# Sheet5_LCD.net
KiCad netlist of a schematic drawn in Altium Designer
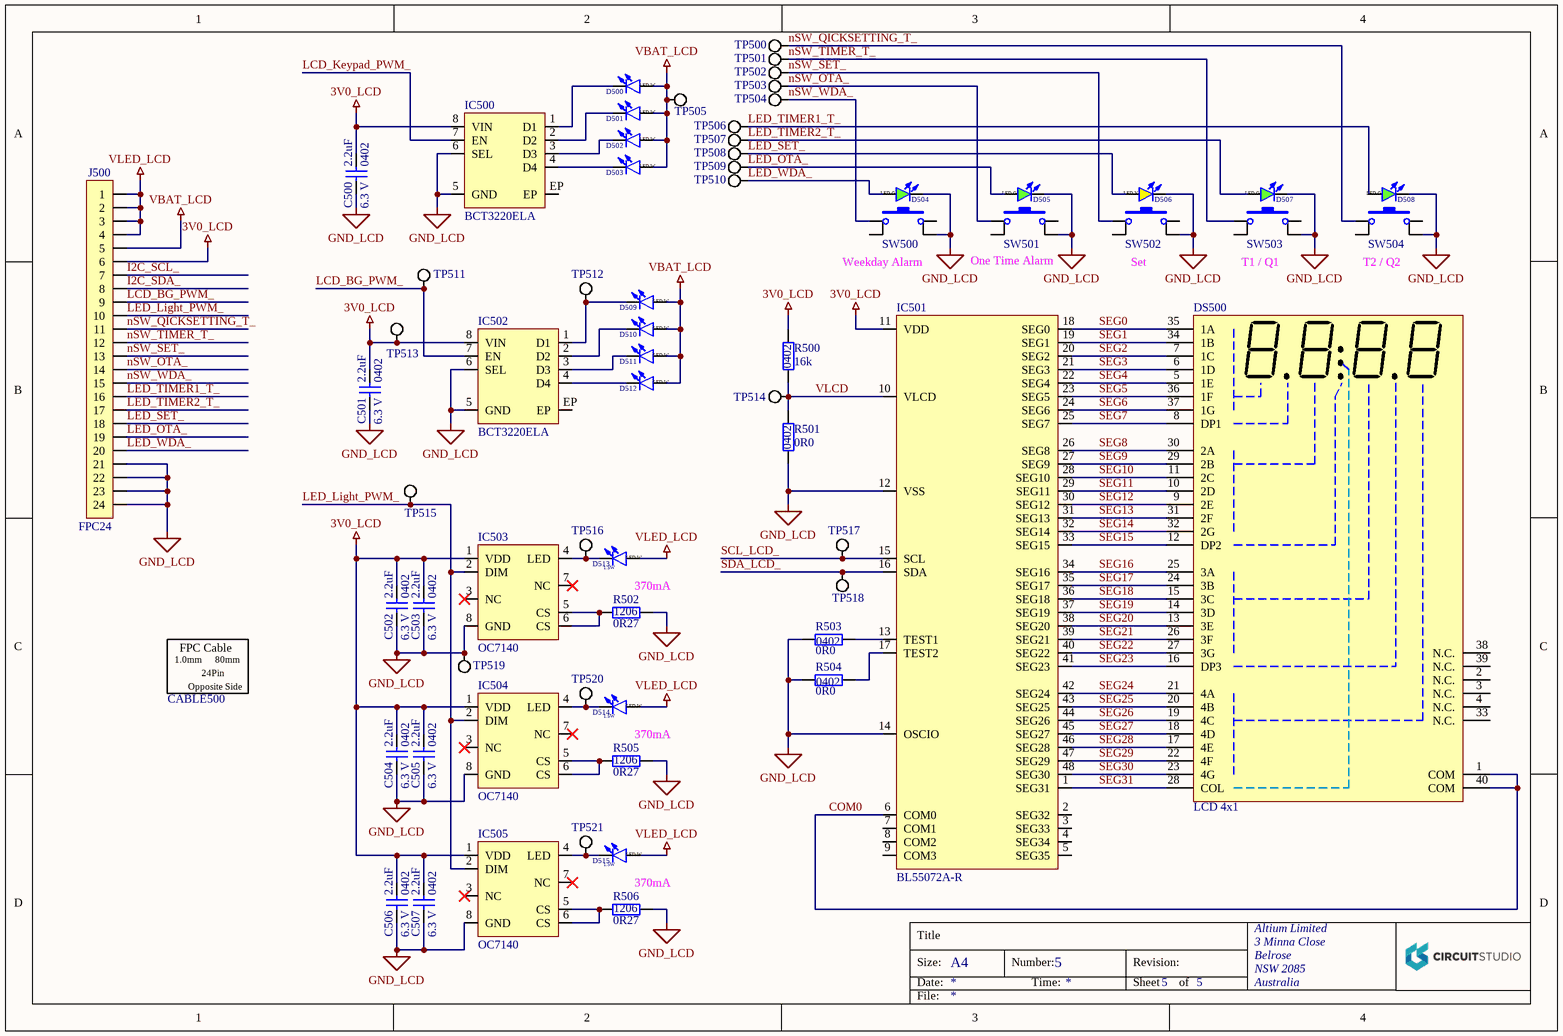
[diagram p0: Sheet5_LCD.SchDoc]

(export (version "E")
  (design (tool "Eeschema 10.0.6"))
  (components
    (comp (ref "C500")
      (value "C 2.2uF 0402 6.3V")
      (footprint "0402")
      (description "CAP CER 2.2UF 6.3V X6T 0402")
      (fields
        (field (name "MANUFACTURER") "Murata Electronics")
        (field (name "MANUFACTURER PART NUMBER") "GRM155D80J225ME95D")
        (field (name "CAPACITANCE") "2.2uF")
        (field (name "VOLTAGE") "6.3 V")
      )
      (libsource (lib "CS_Part_Library") (part "CAP_2.2uF_6V3_0402"))
    )
    (comp (ref "C501")
      (value "C 2.2uF 0402 6.3V")
      (footprint "0402")
      (description "CAP CER 2.2UF 6.3V X6T 0402")
      (fields
        (field (name "MANUFACTURER") "Murata Electronics")
        (field (name "MANUFACTURER PART NUMBER") "GRM155D80J225ME95D")
        (field (name "CAPACITANCE") "2.2uF")
        (field (name "VOLTAGE") "6.3 V")
      )
      (libsource (lib "CS_Part_Library") (part "CAP_2.2uF_6V3_0402"))
    )
    (comp (ref "C502")
      (value "C 2.2uF 0402 6.3V")
      (footprint "0402")
      (description "CAP CER 2.2UF 6.3V X6T 0402")
      (fields
        (field (name "MANUFACTURER") "Murata Electronics")
        (field (name "MANUFACTURER PART NUMBER") "GRM155D80J225ME95D")
        (field (name "CAPACITANCE") "2.2uF")
        (field (name "VOLTAGE") "6.3 V")
      )
      (libsource (lib "CS_Part_Library") (part "CAP_2.2uF_6V3_0402"))
    )
    (comp (ref "C503")
      (value "C 2.2uF 0402 6.3V")
      (footprint "0402")
      (description "CAP CER 2.2UF 6.3V X6T 0402")
      (fields
        (field (name "MANUFACTURER") "Murata Electronics")
        (field (name "MANUFACTURER PART NUMBER") "GRM155D80J225ME95D")
        (field (name "CAPACITANCE") "2.2uF")
        (field (name "VOLTAGE") "6.3 V")
      )
      (libsource (lib "CS_Part_Library") (part "CAP_2.2uF_6V3_0402"))
    )
    (comp (ref "C504")
      (value "C 2.2uF 0402 6.3V")
      (footprint "0402")
      (description "CAP CER 2.2UF 6.3V X6T 0402")
      (fields
        (field (name "MANUFACTURER") "Murata Electronics")
        (field (name "MANUFACTURER PART NUMBER") "GRM155D80J225ME95D")
        (field (name "CAPACITANCE") "2.2uF")
        (field (name "VOLTAGE") "6.3 V")
      )
      (libsource (lib "CS_Part_Library") (part "CAP_2.2uF_6V3_0402"))
    )
    (comp (ref "C505")
      (value "C 2.2uF 0402 6.3V")
      (footprint "0402")
      (description "CAP CER 2.2UF 6.3V X6T 0402")
      (fields
        (field (name "MANUFACTURER") "Murata Electronics")
        (field (name "MANUFACTURER PART NUMBER") "GRM155D80J225ME95D")
        (field (name "CAPACITANCE") "2.2uF")
        (field (name "VOLTAGE") "6.3 V")
      )
      (libsource (lib "CS_Part_Library") (part "CAP_2.2uF_6V3_0402"))
    )
    (comp (ref "C506")
      (value "C 2.2uF 0402 6.3V")
      (footprint "0402")
      (description "CAP CER 2.2UF 6.3V X6T 0402")
      (fields
        (field (name "MANUFACTURER") "Murata Electronics")
        (field (name "MANUFACTURER PART NUMBER") "GRM155D80J225ME95D")
        (field (name "CAPACITANCE") "2.2uF")
        (field (name "VOLTAGE") "6.3 V")
      )
      (libsource (lib "CS_Part_Library") (part "CAP_2.2uF_6V3_0402"))
    )
    (comp (ref "C507")
      (value "C 2.2uF 0402 6.3V")
      (footprint "0402")
      (description "CAP CER 2.2UF 6.3V X6T 0402")
      (fields
        (field (name "MANUFACTURER") "Murata Electronics")
        (field (name "MANUFACTURER PART NUMBER") "GRM155D80J225ME95D")
        (field (name "CAPACITANCE") "2.2uF")
        (field (name "VOLTAGE") "6.3 V")
      )
      (libsource (lib "CS_Part_Library") (part "CAP_2.2uF_6V3_0402"))
    )
    (comp (ref "CABLE500")
      (value "FPC24p80mm")
      (description "FPC Cable 1mm Pitch 24Pin 80mm Opposite Sides")
      (fields
        (field (name "MANUFACTURER") "LX")
        (field (name "MANUFACTURER PART NUMBER") "C50299")
        (field (name "PITCH") "1.0mm")
        (field (name "LENGTH") "80mm")
        (field (name "MODE") "Opposite Side")
        (field (name "NOOFPINS") "24Pin")
      )
      (libsource (lib "Symbols") (part "CABLE_FPC24_80"))
    )
    (comp (ref "D500")
      (value "LED W")
      (footprint "LED_99-218UMC_side")
      (description "LED WHITE SIDE SMD")
      (fields
        (field (name "MANUFACTURER") "Everlight Elec")
        (field (name "MANUFACTURER PART NUMBER") "99-218UMC/1637CD/TR8-T")
      )
      (libsource (lib "CS_Part_Library") (part "D_LED_White_s"))
    )
    (comp (ref "D501")
      (value "LED W")
      (footprint "LED_99-218UMC_side")
      (description "LED WHITE SIDE SMD")
      (fields
        (field (name "MANUFACTURER") "Everlight Elec")
        (field (name "MANUFACTURER PART NUMBER") "99-218UMC/1637CD/TR8-T")
      )
      (libsource (lib "CS_Part_Library") (part "D_LED_White_s"))
    )
    (comp (ref "D502")
      (value "LED W")
      (footprint "LED_99-218UMC_side")
      (description "LED WHITE SIDE SMD")
      (fields
        (field (name "MANUFACTURER") "Everlight Elec")
        (field (name "MANUFACTURER PART NUMBER") "99-218UMC/1637CD/TR8-T")
      )
      (libsource (lib "CS_Part_Library") (part "D_LED_White_s"))
    )
    (comp (ref "D503")
      (value "LED W")
      (footprint "LED_99-218UMC_side")
      (description "LED WHITE SIDE SMD")
      (fields
        (field (name "MANUFACTURER") "Everlight Elec")
        (field (name "MANUFACTURER PART NUMBER") "99-218UMC/1637CD/TR8-T")
      )
      (libsource (lib "CS_Part_Library") (part "D_LED_White_s"))
    )
    (comp (ref "D504")
      (value "LED G")
      (footprint "LED_0603")
      (description "LED GREEN DIFFUSED 0603 SMD")
      (fields
        (field (name "MANUFACTURER") "OSRAM Opto Semiconductors Inc.")
        (field (name "MANUFACTURER PART NUMBER") "LT Q39G-Q1OO-25-1")
      )
      (libsource (lib "CS_Part_Library") (part "D_LED_Green_0603"))
    )
    (comp (ref "D505")
      (value "LED G")
      (footprint "LED_0603")
      (description "LED GREEN DIFFUSED 0603 SMD")
      (fields
        (field (name "MANUFACTURER") "OSRAM Opto Semiconductors Inc.")
        (field (name "MANUFACTURER PART NUMBER") "LT Q39G-Q1OO-25-1")
      )
      (libsource (lib "CS_Part_Library") (part "D_LED_Green_0603"))
    )
    (comp (ref "D506")
      (value "LED Y")
      (footprint "LED_0603")
      (description "LED YELLOW DIFFUSED")
      (fields
        (field (name "MANUFACTURER") "Stanley Electric Co")
        (field (name "MANUFACTURER PART NUMBER") "FKY1111C-TR")
      )
      (libsource (lib "CS_Part_Library") (part "D_LED_Yellow_0603"))
    )
    (comp (ref "D507")
      (value "LED G")
      (footprint "LED_0603")
      (description "LED GREEN DIFFUSED 0603 SMD")
      (fields
        (field (name "MANUFACTURER") "OSRAM Opto Semiconductors Inc.")
        (field (name "MANUFACTURER PART NUMBER") "LT Q39G-Q1OO-25-1")
      )
      (libsource (lib "CS_Part_Library") (part "D_LED_Green_0603"))
    )
    (comp (ref "D508")
      (value "LED G")
      (footprint "LED_0603")
      (description "LED GREEN DIFFUSED 0603 SMD")
      (fields
        (field (name "MANUFACTURER") "OSRAM Opto Semiconductors Inc.")
        (field (name "MANUFACTURER PART NUMBER") "LT Q39G-Q1OO-25-1")
      )
      (libsource (lib "CS_Part_Library") (part "D_LED_Green_0603"))
    )
    (comp (ref "D509")
      (value "LED W")
      (footprint "LED_99-218UMC_side")
      (description "LED WHITE SIDE SMD")
      (fields
        (field (name "MANUFACTURER") "Everlight Elec")
        (field (name "MANUFACTURER PART NUMBER") "99-218UMC/1637CD/TR8-T")
      )
      (libsource (lib "CS_Part_Library") (part "D_LED_White_s"))
    )
    (comp (ref "D510")
      (value "LED W")
      (footprint "LED_99-218UMC_side")
      (description "LED WHITE SIDE SMD")
      (fields
        (field (name "MANUFACTURER") "Everlight Elec")
        (field (name "MANUFACTURER PART NUMBER") "99-218UMC/1637CD/TR8-T")
      )
      (libsource (lib "CS_Part_Library") (part "D_LED_White_s"))
    )
    (comp (ref "D511")
      (value "LED W")
      (footprint "LED_99-218UMC_side")
      (description "LED WHITE SIDE SMD")
      (fields
        (field (name "MANUFACTURER") "Everlight Elec")
        (field (name "MANUFACTURER PART NUMBER") "99-218UMC/1637CD/TR8-T")
      )
      (libsource (lib "CS_Part_Library") (part "D_LED_White_s"))
    )
    (comp (ref "D512")
      (value "LED W")
      (footprint "LED_99-218UMC_side")
      (description "LED WHITE SIDE SMD")
      (fields
        (field (name "MANUFACTURER") "Everlight Elec")
        (field (name "MANUFACTURER PART NUMBER") "99-218UMC/1637CD/TR8-T")
      )
      (libsource (lib "CS_Part_Library") (part "D_LED_White_s"))
    )
    (comp (ref "D513")
      (value "LED W")
      (footprint "LED_3.5x3.15")
      (description "LED XLAMP WARM WHITE 3250K 4SMD")
      (fields
        (field (name "MANUFACTURER") "CreeLED, Inc.")
        (field (name "MANUFACTURER PART NUMBER") "MLEAWT-A1-0000-0003F7")
        (field (name "POWER") "1.5W")
      )
      (libsource (lib "CS_Part_Library") (part "D_LED_W_HP"))
    )
    (comp (ref "D514")
      (value "LED W")
      (footprint "LED_3.5x3.15")
      (description "LED XLAMP WARM WHITE 3250K 4SMD")
      (fields
        (field (name "MANUFACTURER") "CreeLED, Inc.")
        (field (name "MANUFACTURER PART NUMBER") "MLEAWT-A1-0000-0003F7")
        (field (name "POWER") "1.5W")
      )
      (libsource (lib "CS_Part_Library") (part "D_LED_W_HP"))
    )
    (comp (ref "D515")
      (value "LED W")
      (footprint "LED_3.5x3.15")
      (description "LED XLAMP WARM WHITE 3250K 4SMD")
      (fields
        (field (name "MANUFACTURER") "CreeLED, Inc.")
        (field (name "MANUFACTURER PART NUMBER") "MLEAWT-A1-0000-0003F7")
        (field (name "POWER") "1.5W")
      )
      (libsource (lib "CS_Part_Library") (part "D_LED_W_HP"))
    )
    (comp (ref "DS500")
      (value "LCD 4x1")
      (footprint "DISPL_7SEG_4")
      (description "LCD MOD 4 DIG 4 X 1 REFLECTIVE")
      (fields
        (field (name "MANUFACTURER") "Varitronix")
        (field (name "MANUFACTURER PART NUMBER") "VI-402-DP-RC-S")
      )
      (libsource (lib "Symbols") (part "DISPL_7SEG_4x1"))
    )
    (comp (ref "IC500")
      (value "BCT3220ELA")
      (footprint "VDFN-8-EP_2x2")
      (description "IC LED DRIVER 4 CH")
      (fields
        (field (name "MANUFACTURER") "BROADCHIP")
        (field (name "MANUFACTURER PART NUMBER") "BCT3220ELA-TR")
      )
      (libsource (lib "Symbols") (part "IC_LED_cntr_BCT3220ELA"))
    )
    (comp (ref "IC501")
      (value "BL55072A-R")
      (footprint "TSSOP-48")
      (description "IC LCD DRIVER 36SEG TSSOP-48")
      (fields (field (name "MANUFACTURER") "BL(Shanghai Belling)"))
      (libsource (lib "Symbols") (part "IC_LCD_cntr_BL55072A-R"))
    )
    (comp (ref "IC502")
      (value "BCT3220ELA")
      (footprint "VDFN-8-EP_2x2")
      (description "IC LED DRIVER 4 CH")
      (fields
        (field (name "MANUFACTURER") "BROADCHIP")
        (field (name "MANUFACTURER PART NUMBER") "BCT3220ELA-TR")
      )
      (libsource (lib "Symbols") (part "IC_LED_cntr_BCT3220ELA"))
    )
    (comp (ref "IC503")
      (value "OC7140")
      (footprint "SOIC-8-EP")
      (description "IC LED DRIVER 1 CH 2A ESOP8")
      (fields (field (name "MANUFACTURER") "OCX"))
      (libsource (lib "CS_Part_Library") (part "IC_LED_cntr_OC7140"))
    )
    (comp (ref "IC504")
      (value "OC7140")
      (footprint "SOIC-8-EP")
      (description "IC LED DRIVER 1 CH 2A ESOP8")
      (fields (field (name "MANUFACTURER") "OCX"))
      (libsource (lib "CS_Part_Library") (part "IC_LED_cntr_OC7140"))
    )
    (comp (ref "IC505")
      (value "OC7140")
      (footprint "SOIC-8-EP")
      (description "IC LED DRIVER 1 CH 2A ESOP8")
      (fields (field (name "MANUFACTURER") "OCX"))
      (libsource (lib "CS_Part_Library") (part "IC_LED_cntr_OC7140"))
    )
    (comp (ref "J500")
      (value "FPC24")
      (footprint "J_FPC_522712479")
      (description "CONN FPC BOT 24 PIN 1mm Pitch")
      (fields (field (name "MANUFACTURER") "MOLEX") (field (name "MANUFACTURER PART NUMBER") "522712479"))
      (libsource (lib "Symbols") (part "J_FPC24_DS"))
    )
    (comp (ref "R500")
      (value "R 16k 0402")
      (footprint "0402")
      (description "RES 16K OHM 1% 1/16W 0402")
      (fields
        (field (name "MANUFACTURER") "Stackpole Electronics Inc")
        (field (name "MANUFACTURER PART NUMBER") "RMCF0402FT16K0")
        (field (name "RESISTANCE") "16k")
      )
      (libsource (lib "CS_Part_Library") (part "R_16k_0402"))
    )
    (comp (ref "R501")
      (value "R 0R0 0402")
      (footprint "0402")
      (description "RES 0 OHM JUMPER 1/16W 0402")
      (fields
        (field (name "MANUFACTURER") "Stackpole Electronics Inc")
        (field (name "MANUFACTURER PART NUMBER") "RMCF0402ZT0R00")
        (field (name "RESISTANCE") "0R0")
      )
      (libsource (lib "CS_Part_Library") (part "R_0R0_0402"))
    )
    (comp (ref "R502")
      (value "R 0R27 1206")
      (footprint "1206")
      (description "RES 0.27 OHM 1% 1/3W 1206")
      (fields
        (field (name "MANUFACTURER") "RALEC")
        (field (name "MANUFACTURER PART NUMBER") "RTT06R270FTP")
        (field (name "RESISTANCE") "0R27")
      )
      (libsource (lib "CS_Part_Library") (part "R_0R27_1206"))
    )
    (comp (ref "R503")
      (value "R 0R0 0402")
      (footprint "0402")
      (description "RES 0 OHM JUMPER 1/16W 0402")
      (fields
        (field (name "MANUFACTURER") "Stackpole Electronics Inc")
        (field (name "MANUFACTURER PART NUMBER") "RMCF0402ZT0R00")
        (field (name "RESISTANCE") "0R0")
      )
      (libsource (lib "") (part "R_0R0_0402_1"))
    )
    (comp (ref "R504")
      (value "R 0R0 0402")
      (footprint "0402")
      (description "RES 0 OHM JUMPER 1/16W 0402")
      (fields
        (field (name "MANUFACTURER") "Stackpole Electronics Inc")
        (field (name "MANUFACTURER PART NUMBER") "RMCF0402ZT0R00")
        (field (name "RESISTANCE") "0R0")
      )
      (libsource (lib "") (part "R_0R0_0402_1"))
    )
    (comp (ref "R505")
      (value "R 0R27 1206")
      (footprint "1206")
      (description "RES 0.27 OHM 1% 1/3W 1206")
      (fields
        (field (name "MANUFACTURER") "RALEC")
        (field (name "MANUFACTURER PART NUMBER") "RTT06R270FTP")
        (field (name "RESISTANCE") "0R27")
      )
      (libsource (lib "CS_Part_Library") (part "R_0R27_1206"))
    )
    (comp (ref "R506")
      (value "R 0R27 1206")
      (footprint "1206")
      (description "RES 0.27 OHM 1% 1/3W 1206")
      (fields
        (field (name "MANUFACTURER") "RALEC")
        (field (name "MANUFACTURER PART NUMBER") "RTT06R270FTP")
        (field (name "RESISTANCE") "0R27")
      )
      (libsource (lib "CS_Part_Library") (part "R_0R27_1206"))
    )
    (comp (ref "SW500")
      (value "SW")
      (footprint "SW_BRIGHT_6.1x6.1")
      (description "SWITCH TACTILE SW-SMD")
      (fields
        (field (name "MANUFACTURER") "BRIGHT")
        (field (name "MANUFACTURER PART NUMBER") "TSA063G50-250")
      )
      (libsource (lib "CS_Part_Library") (part "SW_TactileSW_V_2"))
    )
    (comp (ref "SW501")
      (value "SW")
      (footprint "SW_BRIGHT_6.1x6.1")
      (description "SWITCH TACTILE SW-SMD")
      (fields
        (field (name "MANUFACTURER") "BRIGHT")
        (field (name "MANUFACTURER PART NUMBER") "TSA063G50-250")
      )
      (libsource (lib "CS_Part_Library") (part "SW_TactileSW_V_2"))
    )
    (comp (ref "SW502")
      (value "SW")
      (footprint "SW_BRIGHT_6.1x6.1")
      (description "SWITCH TACTILE SW-SMD")
      (fields
        (field (name "MANUFACTURER") "BRIGHT")
        (field (name "MANUFACTURER PART NUMBER") "TSA063G50-250")
      )
      (libsource (lib "CS_Part_Library") (part "SW_TactileSW_V_2"))
    )
    (comp (ref "SW503")
      (value "SW")
      (footprint "SW_BRIGHT_6.1x6.1")
      (description "SWITCH TACTILE SW-SMD")
      (fields
        (field (name "MANUFACTURER") "BRIGHT")
        (field (name "MANUFACTURER PART NUMBER") "TSA063G50-250")
      )
      (libsource (lib "CS_Part_Library") (part "SW_TactileSW_V_2"))
    )
    (comp (ref "SW504")
      (value "SW")
      (footprint "SW_BRIGHT_6.1x6.1")
      (description "SWITCH TACTILE SW-SMD")
      (fields
        (field (name "MANUFACTURER") "BRIGHT")
        (field (name "MANUFACTURER PART NUMBER") "TSA063G50-250")
      )
      (libsource (lib "CS_Part_Library") (part "SW_TactileSW_V_2"))
    )
    (comp (ref "TP500")
      (value "TP")
      (footprint "TP_1mm")
      (description "Test Point 1mm")
      (libsource (lib "CS_Part_Library") (part "TP_1mm"))
    )
    (comp (ref "TP501")
      (value "TP")
      (footprint "TP_1mm")
      (description "Test Point 1mm")
      (libsource (lib "CS_Part_Library") (part "TP_1mm"))
    )
    (comp (ref "TP502")
      (value "TP")
      (footprint "TP_1mm")
      (description "Test Point 1mm")
      (libsource (lib "CS_Part_Library") (part "TP_1mm"))
    )
    (comp (ref "TP503")
      (value "TP")
      (footprint "TP_1mm")
      (description "Test Point 1mm")
      (libsource (lib "CS_Part_Library") (part "TP_1mm"))
    )
    (comp (ref "TP504")
      (value "TP")
      (footprint "TP_1mm")
      (description "Test Point 1mm")
      (libsource (lib "CS_Part_Library") (part "TP_1mm"))
    )
    (comp (ref "TP505")
      (value "TP")
      (footprint "TP_1mm")
      (description "Test Point 1mm")
      (libsource (lib "CS_Part_Library") (part "TP_1mm"))
    )
    (comp (ref "TP506")
      (value "TP")
      (footprint "TP_1mm")
      (description "Test Point 1mm")
      (libsource (lib "CS_Part_Library") (part "TP_1mm"))
    )
    (comp (ref "TP507")
      (value "TP")
      (footprint "TP_1mm")
      (description "Test Point 1mm")
      (libsource (lib "CS_Part_Library") (part "TP_1mm"))
    )
    (comp (ref "TP508")
      (value "TP")
      (footprint "TP_1mm")
      (description "Test Point 1mm")
      (libsource (lib "CS_Part_Library") (part "TP_1mm"))
    )
    (comp (ref "TP509")
      (value "TP")
      (footprint "TP_1mm")
      (description "Test Point 1mm")
      (libsource (lib "CS_Part_Library") (part "TP_1mm"))
    )
    (comp (ref "TP510")
      (value "TP")
      (footprint "TP_1mm")
      (description "Test Point 1mm")
      (libsource (lib "CS_Part_Library") (part "TP_1mm"))
    )
    (comp (ref "TP511")
      (value "TP")
      (footprint "TP_1mm")
      (description "Test Point 1mm")
      (libsource (lib "CS_Part_Library") (part "TP_1mm"))
    )
    (comp (ref "TP512")
      (value "TP")
      (footprint "TP_1mm")
      (description "Test Point 1mm")
      (libsource (lib "CS_Part_Library") (part "TP_1mm"))
    )
    (comp (ref "TP513")
      (value "TP")
      (footprint "TP_1mm")
      (description "Test Point 1mm")
      (libsource (lib "CS_Part_Library") (part "TP_1mm"))
    )
    (comp (ref "TP514")
      (value "TP")
      (footprint "TP_1mm")
      (description "Test Point 1mm")
      (libsource (lib "CS_Part_Library") (part "TP_1mm"))
    )
    (comp (ref "TP515")
      (value "TP")
      (footprint "TP_1mm")
      (description "Test Point 1mm")
      (libsource (lib "CS_Part_Library") (part "TP_1mm"))
    )
    (comp (ref "TP516")
      (value "TP")
      (footprint "TP_1mm")
      (description "Test Point 1mm")
      (libsource (lib "CS_Part_Library") (part "TP_1mm"))
    )
    (comp (ref "TP517")
      (value "TP")
      (footprint "TP_1mm")
      (description "Test Point 1mm")
      (libsource (lib "CS_Part_Library") (part "TP_1mm"))
    )
    (comp (ref "TP518")
      (value "TP")
      (footprint "TP_1mm")
      (description "Test Point 1mm")
      (libsource (lib "CS_Part_Library") (part "TP_1mm"))
    )
    (comp (ref "TP519")
      (value "TP")
      (footprint "TP_1mm")
      (description "Test Point 1mm")
      (libsource (lib "CS_Part_Library") (part "TP_1mm"))
    )
    (comp (ref "TP520")
      (value "TP")
      (footprint "TP_1mm")
      (description "Test Point 1mm")
      (libsource (lib "CS_Part_Library") (part "TP_1mm"))
    )
    (comp (ref "TP521")
      (value "TP")
      (footprint "TP_1mm")
      (description "Test Point 1mm")
      (libsource (lib "CS_Part_Library") (part "TP_1mm"))
    )
  )
  (nets
    (net (code "1") (name "/COM0") (class "Default")
      (node (ref "DS500") (pin "1") (pinfunction "COM_1") (pintype "passive"))
      (node (ref "DS500") (pin "40") (pinfunction "COM_40") (pintype "passive"))
      (node (ref "IC501") (pin "6") (pinfunction "COM0_6") (pintype "passive"))
    )
    (net (code "2") (name "/I2C_SCL_") (class "Default")
      (node (ref "J500") (pin "7") (pinfunction "7_7") (pintype "passive"))
    )
    (net (code "3") (name "/I2C_SDA_") (class "Default")
      (node (ref "J500") (pin "8") (pinfunction "8_8") (pintype "passive"))
    )
    (net (code "4") (name "/LCD_BG_PWM_") (class "Default")
      (node (ref "IC502") (pin "7") (pinfunction "EN_7") (pintype "passive"))
      (node (ref "J500") (pin "9") (pinfunction "9_9") (pintype "passive"))
      (node (ref "TP511") (pin "1") (pinfunction "TP_1") (pintype "passive"))
    )
    (net (code "5") (name "/LCD_Keypad_PWM_") (class "Default")
      (node (ref "IC500") (pin "7") (pinfunction "EN_7") (pintype "passive"))
    )
    (net (code "6") (name "/LED_Light_PWM_") (class "Default")
      (node (ref "IC503") (pin "2") (pinfunction "DIM_2") (pintype "passive"))
      (node (ref "IC504") (pin "2") (pinfunction "DIM_2") (pintype "passive"))
      (node (ref "IC505") (pin "2") (pinfunction "DIM_2") (pintype "passive"))
      (node (ref "J500") (pin "10") (pinfunction "10_10") (pintype "passive"))
      (node (ref "TP515") (pin "1") (pinfunction "TP_1") (pintype "passive"))
    )
    (net (code "7") (name "/LED_OTA_") (class "Default")
      (node (ref "D505") (pin "A") (pinfunction "A_A") (pintype "passive"))
      (node (ref "J500") (pin "19") (pinfunction "19_19") (pintype "passive"))
      (node (ref "TP509") (pin "1") (pinfunction "TP_1") (pintype "passive"))
    )
    (net (code "8") (name "/LED_SET_") (class "Default")
      (node (ref "D506") (pin "A") (pinfunction "A_A") (pintype "passive"))
      (node (ref "J500") (pin "18") (pinfunction "18_18") (pintype "passive"))
      (node (ref "TP508") (pin "1") (pinfunction "TP_1") (pintype "passive"))
    )
    (net (code "9") (name "/LED_TIMER1_T_") (class "Default")
      (node (ref "D508") (pin "A") (pinfunction "A_A") (pintype "passive"))
      (node (ref "J500") (pin "16") (pinfunction "16_16") (pintype "passive"))
      (node (ref "TP506") (pin "1") (pinfunction "TP_1") (pintype "passive"))
    )
    (net (code "10") (name "/LED_TIMER2_T_") (class "Default")
      (node (ref "D507") (pin "A") (pinfunction "A_A") (pintype "passive"))
      (node (ref "J500") (pin "17") (pinfunction "17_17") (pintype "passive"))
      (node (ref "TP507") (pin "1") (pinfunction "TP_1") (pintype "passive"))
    )
    (net (code "11") (name "/LED_WDA_") (class "Default")
      (node (ref "D504") (pin "A") (pinfunction "A_A") (pintype "passive"))
      (node (ref "J500") (pin "20") (pinfunction "20_20") (pintype "passive"))
      (node (ref "TP510") (pin "1") (pinfunction "TP_1") (pintype "passive"))
    )
    (net (code "12") (name "/SCL_LCD_") (class "Default")
      (node (ref "IC501") (pin "15") (pinfunction "SCL_15") (pintype "passive"))
      (node (ref "TP517") (pin "1") (pinfunction "TP_1") (pintype "passive"))
    )
    (net (code "13") (name "/SDA_LCD_") (class "Default")
      (node (ref "IC501") (pin "16") (pinfunction "SDA_16") (pintype "passive"))
      (node (ref "TP518") (pin "1") (pinfunction "TP_1") (pintype "passive"))
    )
    (net (code "14") (name "/SEG0") (class "Default")
      (node (ref "DS500") (pin "35") (pinfunction "1A_35") (pintype "passive"))
      (node (ref "IC501") (pin "18") (pinfunction "SEG0_18") (pintype "passive"))
    )
    (net (code "15") (name "/SEG1") (class "Default")
      (node (ref "DS500") (pin "34") (pinfunction "1B_34") (pintype "passive"))
      (node (ref "IC501") (pin "19") (pinfunction "SEG1_19") (pintype "passive"))
    )
    (net (code "16") (name "/SEG2") (class "Default")
      (node (ref "DS500") (pin "7") (pinfunction "1C_7") (pintype "passive"))
      (node (ref "IC501") (pin "20") (pinfunction "SEG2_20") (pintype "passive"))
    )
    (net (code "17") (name "/SEG3") (class "Default")
      (node (ref "DS500") (pin "6") (pinfunction "1D_6") (pintype "passive"))
      (node (ref "IC501") (pin "21") (pinfunction "SEG3_21") (pintype "passive"))
    )
    (net (code "18") (name "/SEG4") (class "Default")
      (node (ref "DS500") (pin "5") (pinfunction "1E_5") (pintype "passive"))
      (node (ref "IC501") (pin "22") (pinfunction "SEG4_22") (pintype "passive"))
    )
    (net (code "19") (name "/SEG5") (class "Default")
      (node (ref "DS500") (pin "36") (pinfunction "1F_36") (pintype "passive"))
      (node (ref "IC501") (pin "23") (pinfunction "SEG5_23") (pintype "passive"))
    )
    (net (code "20") (name "/SEG6") (class "Default")
      (node (ref "DS500") (pin "37") (pinfunction "1G_37") (pintype "passive"))
      (node (ref "IC501") (pin "24") (pinfunction "SEG6_24") (pintype "passive"))
    )
    (net (code "21") (name "/SEG7") (class "Default")
      (node (ref "DS500") (pin "8") (pinfunction "DP1_8") (pintype "passive"))
      (node (ref "IC501") (pin "25") (pinfunction "SEG7_25") (pintype "passive"))
    )
    (net (code "22") (name "/SEG8") (class "Default")
      (node (ref "DS500") (pin "30") (pinfunction "2A_30") (pintype "passive"))
      (node (ref "IC501") (pin "26") (pinfunction "SEG8_26") (pintype "passive"))
    )
    (net (code "23") (name "/SEG9") (class "Default")
      (node (ref "DS500") (pin "29") (pinfunction "2B_29") (pintype "passive"))
      (node (ref "IC501") (pin "27") (pinfunction "SEG9_27") (pintype "passive"))
    )
    (net (code "24") (name "/SEG10") (class "Default")
      (node (ref "DS500") (pin "11") (pinfunction "2C_11") (pintype "passive"))
      (node (ref "IC501") (pin "28") (pinfunction "SEG10_28") (pintype "passive"))
    )
    (net (code "25") (name "/SEG11") (class "Default")
      (node (ref "DS500") (pin "10") (pinfunction "2D_10") (pintype "passive"))
      (node (ref "IC501") (pin "29") (pinfunction "SEG11_29") (pintype "passive"))
    )
    (net (code "26") (name "/SEG12") (class "Default")
      (node (ref "DS500") (pin "9") (pinfunction "2E_9") (pintype "passive"))
      (node (ref "IC501") (pin "30") (pinfunction "SEG12_30") (pintype "passive"))
    )
    (net (code "27") (name "/SEG13") (class "Default")
      (node (ref "DS500") (pin "31") (pinfunction "2F_31") (pintype "passive"))
      (node (ref "IC501") (pin "31") (pinfunction "SEG13_31") (pintype "passive"))
    )
    (net (code "28") (name "/SEG14") (class "Default")
      (node (ref "DS500") (pin "32") (pinfunction "2G_32") (pintype "passive"))
      (node (ref "IC501") (pin "32") (pinfunction "SEG14_32") (pintype "passive"))
    )
    (net (code "29") (name "/SEG15") (class "Default")
      (node (ref "DS500") (pin "12") (pinfunction "DP2_12") (pintype "passive"))
      (node (ref "IC501") (pin "33") (pinfunction "SEG15_33") (pintype "passive"))
    )
    (net (code "30") (name "/SEG16") (class "Default")
      (node (ref "DS500") (pin "25") (pinfunction "3A_25") (pintype "passive"))
      (node (ref "IC501") (pin "34") (pinfunction "SEG16_34") (pintype "passive"))
    )
    (net (code "31") (name "/SEG17") (class "Default")
      (node (ref "DS500") (pin "24") (pinfunction "3B_24") (pintype "passive"))
      (node (ref "IC501") (pin "35") (pinfunction "SEG17_35") (pintype "passive"))
    )
    (net (code "32") (name "/SEG18") (class "Default")
      (node (ref "DS500") (pin "15") (pinfunction "3C_15") (pintype "passive"))
      (node (ref "IC501") (pin "36") (pinfunction "SEG18_36") (pintype "passive"))
    )
    (net (code "33") (name "/SEG19") (class "Default")
      (node (ref "DS500") (pin "14") (pinfunction "3D_14") (pintype "passive"))
      (node (ref "IC501") (pin "37") (pinfunction "SEG19_37") (pintype "passive"))
    )
    (net (code "34") (name "/SEG20") (class "Default")
      (node (ref "DS500") (pin "13") (pinfunction "3E_13") (pintype "passive"))
      (node (ref "IC501") (pin "38") (pinfunction "SEG20_38") (pintype "passive"))
    )
    (net (code "35") (name "/SEG21") (class "Default")
      (node (ref "DS500") (pin "26") (pinfunction "3F_26") (pintype "passive"))
      (node (ref "IC501") (pin "39") (pinfunction "SEG21_39") (pintype "passive"))
    )
    (net (code "36") (name "/SEG22") (class "Default")
      (node (ref "DS500") (pin "27") (pinfunction "3G_27") (pintype "passive"))
      (node (ref "IC501") (pin "40") (pinfunction "SEG22_40") (pintype "passive"))
    )
    (net (code "37") (name "/SEG23") (class "Default")
      (node (ref "DS500") (pin "16") (pinfunction "DP3_16") (pintype "passive"))
      (node (ref "IC501") (pin "41") (pinfunction "SEG23_41") (pintype "passive"))
    )
    (net (code "38") (name "/SEG24") (class "Default")
      (node (ref "DS500") (pin "21") (pinfunction "4A_21") (pintype "passive"))
      (node (ref "IC501") (pin "42") (pinfunction "SEG24_42") (pintype "passive"))
    )
    (net (code "39") (name "/SEG25") (class "Default")
      (node (ref "DS500") (pin "20") (pinfunction "4B_20") (pintype "passive"))
      (node (ref "IC501") (pin "43") (pinfunction "SEG25_43") (pintype "passive"))
    )
    (net (code "40") (name "/SEG26") (class "Default")
      (node (ref "DS500") (pin "19") (pinfunction "4C_19") (pintype "passive"))
      (node (ref "IC501") (pin "44") (pinfunction "SEG26_44") (pintype "passive"))
    )
    (net (code "41") (name "/SEG27") (class "Default")
      (node (ref "DS500") (pin "18") (pinfunction "4D_18") (pintype "passive"))
      (node (ref "IC501") (pin "45") (pinfunction "SEG27_45") (pintype "passive"))
    )
    (net (code "42") (name "/SEG28") (class "Default")
      (node (ref "DS500") (pin "17") (pinfunction "4E_17") (pintype "passive"))
      (node (ref "IC501") (pin "46") (pinfunction "SEG28_46") (pintype "passive"))
    )
    (net (code "43") (name "/SEG29") (class "Default")
      (node (ref "DS500") (pin "22") (pinfunction "4F_22") (pintype "passive"))
      (node (ref "IC501") (pin "47") (pinfunction "SEG29_47") (pintype "passive"))
    )
    (net (code "44") (name "/SEG30") (class "Default")
      (node (ref "DS500") (pin "23") (pinfunction "4G_23") (pintype "passive"))
      (node (ref "IC501") (pin "48") (pinfunction "SEG30_48") (pintype "passive"))
    )
    (net (code "45") (name "/SEG31") (class "Default")
      (node (ref "DS500") (pin "28") (pinfunction "COL_28") (pintype "passive"))
      (node (ref "IC501") (pin "1") (pinfunction "SEG31_1") (pintype "passive"))
    )
    (net (code "46") (name "/VLCD") (class "Default")
      (node (ref "IC501") (pin "10") (pinfunction "VLCD_10") (pintype "passive"))
      (node (ref "R500") (pin "1") (pinfunction "1_1") (pintype "passive"))
      (node (ref "R501") (pin "2") (pinfunction "2_2") (pintype "passive"))
      (node (ref "TP514") (pin "1") (pinfunction "TP_1") (pintype "passive"))
    )
    (net (code "47") (name "/nSW_OTA_") (class "Default")
      (node (ref "J500") (pin "14") (pinfunction "14_14") (pintype "passive"))
      (node (ref "SW501") (pin "1") (pinfunction "1_1") (pintype "passive"))
      (node (ref "TP503") (pin "1") (pinfunction "TP_1") (pintype "passive"))
    )
    (net (code "48") (name "/nSW_QICKSETTING_T_") (class "Default")
      (node (ref "J500") (pin "11") (pinfunction "11_11") (pintype "passive"))
      (node (ref "SW504") (pin "1") (pinfunction "1_1") (pintype "passive"))
      (node (ref "TP500") (pin "1") (pinfunction "TP_1") (pintype "passive"))
    )
    (net (code "49") (name "/nSW_SET_") (class "Default")
      (node (ref "J500") (pin "13") (pinfunction "13_13") (pintype "passive"))
      (node (ref "SW502") (pin "1") (pinfunction "1_1") (pintype "passive"))
      (node (ref "TP502") (pin "1") (pinfunction "TP_1") (pintype "passive"))
    )
    (net (code "50") (name "/nSW_TIMER_T_") (class "Default")
      (node (ref "J500") (pin "12") (pinfunction "12_12") (pintype "passive"))
      (node (ref "SW503") (pin "1") (pinfunction "1_1") (pintype "passive"))
      (node (ref "TP501") (pin "1") (pinfunction "TP_1") (pintype "passive"))
    )
    (net (code "51") (name "/nSW_WDA_") (class "Default")
      (node (ref "J500") (pin "15") (pinfunction "15_15") (pintype "passive"))
      (node (ref "SW500") (pin "1") (pinfunction "1_1") (pintype "passive"))
      (node (ref "TP504") (pin "1") (pinfunction "TP_1") (pintype "passive"))
    )
    (net (code "52") (name "3V0_LCD") (class "Default")
      (node (ref "C500") (pin "2") (pinfunction "2_2") (pintype "passive"))
      (node (ref "C501") (pin "2") (pinfunction "2_2") (pintype "passive"))
      (node (ref "C502") (pin "2") (pinfunction "2_2") (pintype "passive"))
      (node (ref "C503") (pin "2") (pinfunction "2_2") (pintype "passive"))
      (node (ref "C504") (pin "2") (pinfunction "2_2") (pintype "passive"))
      (node (ref "C505") (pin "2") (pinfunction "2_2") (pintype "passive"))
      (node (ref "C506") (pin "2") (pinfunction "2_2") (pintype "passive"))
      (node (ref "C507") (pin "2") (pinfunction "2_2") (pintype "passive"))
      (node (ref "IC500") (pin "8") (pinfunction "VIN_8") (pintype "passive"))
      (node (ref "IC501") (pin "11") (pinfunction "VDD_11") (pintype "passive"))
      (node (ref "IC502") (pin "8") (pinfunction "VIN_8") (pintype "passive"))
      (node (ref "IC503") (pin "1") (pinfunction "VDD_1") (pintype "passive"))
      (node (ref "IC504") (pin "1") (pinfunction "VDD_1") (pintype "passive"))
      (node (ref "IC505") (pin "1") (pinfunction "VDD_1") (pintype "passive"))
      (node (ref "J500") (pin "6") (pinfunction "6_6") (pintype "passive"))
      (node (ref "R500") (pin "2") (pinfunction "2_2") (pintype "passive"))
      (node (ref "TP513") (pin "1") (pinfunction "TP_1") (pintype "passive"))
    )
    (net (code "53") (name "GND_LCD") (class "Default")
      (node (ref "C500") (pin "1") (pinfunction "1_1") (pintype "passive"))
      (node (ref "C501") (pin "1") (pinfunction "1_1") (pintype "passive"))
      (node (ref "C502") (pin "1") (pinfunction "1_1") (pintype "passive"))
      (node (ref "C503") (pin "1") (pinfunction "1_1") (pintype "passive"))
      (node (ref "C504") (pin "1") (pinfunction "1_1") (pintype "passive"))
      (node (ref "C505") (pin "1") (pinfunction "1_1") (pintype "passive"))
      (node (ref "C506") (pin "1") (pinfunction "1_1") (pintype "passive"))
      (node (ref "C507") (pin "1") (pinfunction "1_1") (pintype "passive"))
      (node (ref "D504") (pin "K") (pinfunction "K_K") (pintype "passive"))
      (node (ref "D505") (pin "K") (pinfunction "K_K") (pintype "passive"))
      (node (ref "D506") (pin "K") (pinfunction "K_K") (pintype "passive"))
      (node (ref "D507") (pin "K") (pinfunction "K_K") (pintype "passive"))
      (node (ref "D508") (pin "K") (pinfunction "K_K") (pintype "passive"))
      (node (ref "IC500") (pin "5") (pinfunction "GND_5") (pintype "passive"))
      (node (ref "IC500") (pin "6") (pinfunction "SEL_6") (pintype "passive"))
      (node (ref "IC501") (pin "12") (pinfunction "VSS_12") (pintype "passive"))
      (node (ref "IC501") (pin "14") (pinfunction "OSCIO_14") (pintype "passive"))
      (node (ref "IC502") (pin "5") (pinfunction "GND_5") (pintype "passive"))
      (node (ref "IC502") (pin "6") (pinfunction "SEL_6") (pintype "passive"))
      (node (ref "IC503") (pin "8") (pinfunction "GND_8") (pintype "passive"))
      (node (ref "IC504") (pin "8") (pinfunction "GND_8") (pintype "passive"))
      (node (ref "IC505") (pin "8") (pinfunction "GND_8") (pintype "passive"))
      (node (ref "J500") (pin "21") (pinfunction "21_21") (pintype "passive"))
      (node (ref "J500") (pin "22") (pinfunction "22_22") (pintype "passive"))
      (node (ref "J500") (pin "23") (pinfunction "23_23") (pintype "passive"))
      (node (ref "J500") (pin "24") (pinfunction "24_24") (pintype "passive"))
      (node (ref "R501") (pin "1") (pinfunction "1_1") (pintype "passive"))
      (node (ref "R502") (pin "2") (pinfunction "2_2") (pintype "passive"))
      (node (ref "R503") (pin "2") (pinfunction "2_2") (pintype "passive"))
      (node (ref "R504") (pin "2") (pinfunction "2_2") (pintype "passive"))
      (node (ref "R505") (pin "2") (pinfunction "2_2") (pintype "passive"))
      (node (ref "R506") (pin "2") (pinfunction "2_2") (pintype "passive"))
      (node (ref "SW500") (pin "4") (pinfunction "4_4") (pintype "passive"))
      (node (ref "SW501") (pin "4") (pinfunction "4_4") (pintype "passive"))
      (node (ref "SW502") (pin "4") (pinfunction "4_4") (pintype "passive"))
      (node (ref "SW503") (pin "4") (pinfunction "4_4") (pintype "passive"))
      (node (ref "SW504") (pin "4") (pinfunction "4_4") (pintype "passive"))
      (node (ref "TP519") (pin "1") (pinfunction "TP_1") (pintype "passive"))
    )
    (net (code "54") (name "Net-(D500-K)") (class "Default")
      (node (ref "D500") (pin "1") (pinfunction "K_1") (pintype "passive"))
      (node (ref "IC500") (pin "1") (pinfunction "D1_1") (pintype "passive"))
    )
    (net (code "55") (name "Net-(D501-K)") (class "Default")
      (node (ref "D501") (pin "1") (pinfunction "K_1") (pintype "passive"))
      (node (ref "IC500") (pin "2") (pinfunction "D2_2") (pintype "passive"))
    )
    (net (code "56") (name "Net-(D502-K)") (class "Default")
      (node (ref "D502") (pin "1") (pinfunction "K_1") (pintype "passive"))
      (node (ref "IC500") (pin "3") (pinfunction "D3_3") (pintype "passive"))
    )
    (net (code "57") (name "Net-(D503-K)") (class "Default")
      (node (ref "D503") (pin "1") (pinfunction "K_1") (pintype "passive"))
      (node (ref "IC500") (pin "4") (pinfunction "D4_4") (pintype "passive"))
    )
    (net (code "58") (name "Net-(D509-K)") (class "Default")
      (node (ref "D509") (pin "1") (pinfunction "K_1") (pintype "passive"))
      (node (ref "IC502") (pin "1") (pinfunction "D1_1") (pintype "passive"))
      (node (ref "TP512") (pin "1") (pinfunction "TP_1") (pintype "passive"))
    )
    (net (code "59") (name "Net-(D510-K)") (class "Default")
      (node (ref "D510") (pin "1") (pinfunction "K_1") (pintype "passive"))
      (node (ref "IC502") (pin "2") (pinfunction "D2_2") (pintype "passive"))
    )
    (net (code "60") (name "Net-(D511-K)") (class "Default")
      (node (ref "D511") (pin "1") (pinfunction "K_1") (pintype "passive"))
      (node (ref "IC502") (pin "3") (pinfunction "D3_3") (pintype "passive"))
    )
    (net (code "61") (name "Net-(D512-K)") (class "Default")
      (node (ref "D512") (pin "1") (pinfunction "K_1") (pintype "passive"))
      (node (ref "IC502") (pin "4") (pinfunction "D4_4") (pintype "passive"))
    )
    (net (code "62") (name "Net-(IC501-TEST1)") (class "Default")
      (node (ref "IC501") (pin "13") (pinfunction "TEST1_13") (pintype "passive"))
      (node (ref "R503") (pin "1") (pinfunction "1_1") (pintype "passive"))
    )
    (net (code "63") (name "Net-(IC501-TEST2)") (class "Default")
      (node (ref "IC501") (pin "17") (pinfunction "TEST2_17") (pintype "passive"))
      (node (ref "R504") (pin "1") (pinfunction "1_1") (pintype "passive"))
    )
    (net (code "64") (name "Net-(IC503-CS-Pad5)") (class "Default")
      (node (ref "IC503") (pin "5") (pinfunction "CS_5") (pintype "passive"))
      (node (ref "IC503") (pin "6") (pinfunction "CS_6") (pintype "passive"))
      (node (ref "R502") (pin "1") (pinfunction "1_1") (pintype "passive"))
    )
    (net (code "65") (name "Net-(IC503-LED)") (class "Default")
      (node (ref "D513") (pin "K") (pinfunction "K_K") (pintype "passive"))
      (node (ref "IC503") (pin "4") (pinfunction "LED_4") (pintype "passive"))
      (node (ref "TP516") (pin "1") (pinfunction "TP_1") (pintype "passive"))
    )
    (net (code "66") (name "Net-(IC504-CS-Pad5)") (class "Default")
      (node (ref "IC504") (pin "5") (pinfunction "CS_5") (pintype "passive"))
      (node (ref "IC504") (pin "6") (pinfunction "CS_6") (pintype "passive"))
      (node (ref "R505") (pin "1") (pinfunction "1_1") (pintype "passive"))
    )
    (net (code "67") (name "Net-(IC504-LED)") (class "Default")
      (node (ref "D514") (pin "K") (pinfunction "K_K") (pintype "passive"))
      (node (ref "IC504") (pin "4") (pinfunction "LED_4") (pintype "passive"))
      (node (ref "TP520") (pin "1") (pinfunction "TP_1") (pintype "passive"))
    )
    (net (code "68") (name "Net-(IC505-CS-Pad5)") (class "Default")
      (node (ref "IC505") (pin "5") (pinfunction "CS_5") (pintype "passive"))
      (node (ref "IC505") (pin "6") (pinfunction "CS_6") (pintype "passive"))
      (node (ref "R506") (pin "1") (pinfunction "1_1") (pintype "passive"))
    )
    (net (code "69") (name "Net-(IC505-LED)") (class "Default")
      (node (ref "D515") (pin "K") (pinfunction "K_K") (pintype "passive"))
      (node (ref "IC505") (pin "4") (pinfunction "LED_4") (pintype "passive"))
      (node (ref "TP521") (pin "1") (pinfunction "TP_1") (pintype "passive"))
    )
    (net (code "70") (name "VBAT_LCD") (class "Default")
      (node (ref "D500") (pin "2") (pinfunction "A_2") (pintype "passive"))
      (node (ref "D501") (pin "2") (pinfunction "A_2") (pintype "passive"))
      (node (ref "D502") (pin "2") (pinfunction "A_2") (pintype "passive"))
      (node (ref "D503") (pin "2") (pinfunction "A_2") (pintype "passive"))
      (node (ref "D509") (pin "2") (pinfunction "A_2") (pintype "passive"))
      (node (ref "D510") (pin "2") (pinfunction "A_2") (pintype "passive"))
      (node (ref "D511") (pin "2") (pinfunction "A_2") (pintype "passive"))
      (node (ref "D512") (pin "2") (pinfunction "A_2") (pintype "passive"))
      (node (ref "J500") (pin "5") (pinfunction "5_5") (pintype "passive"))
      (node (ref "TP505") (pin "1") (pinfunction "TP_1") (pintype "passive"))
    )
    (net (code "71") (name "VLED_LCD") (class "Default")
      (node (ref "D513") (pin "A") (pinfunction "A_A") (pintype "passive"))
      (node (ref "D514") (pin "A") (pinfunction "A_A") (pintype "passive"))
      (node (ref "D515") (pin "A") (pinfunction "A_A") (pintype "passive"))
      (node (ref "J500") (pin "1") (pinfunction "1_1") (pintype "passive"))
      (node (ref "J500") (pin "2") (pinfunction "2_2") (pintype "passive"))
      (node (ref "J500") (pin "3") (pinfunction "3_3") (pintype "passive"))
      (node (ref "J500") (pin "4") (pinfunction "4_4") (pintype "passive"))
    )
    (net (code "72") (name "unconnected-(DS500-N.C.-Pad2)") (class "Default")
      (node (ref "DS500") (pin "2") (pinfunction "N.C._2") (pintype "passive"))
    )
    (net (code "73") (name "unconnected-(DS500-N.C.-Pad3)") (class "Default")
      (node (ref "DS500") (pin "3") (pinfunction "N.C._3") (pintype "passive"))
    )
    (net (code "74") (name "unconnected-(DS500-N.C.-Pad4)") (class "Default")
      (node (ref "DS500") (pin "4") (pinfunction "N.C._4") (pintype "passive"))
    )
    (net (code "75") (name "unconnected-(DS500-N.C.-Pad33)") (class "Default")
      (node (ref "DS500") (pin "33") (pinfunction "N.C._33") (pintype "passive"))
    )
    (net (code "76") (name "unconnected-(DS500-N.C.-Pad38)") (class "Default")
      (node (ref "DS500") (pin "38") (pinfunction "N.C._38") (pintype "passive"))
    )
    (net (code "77") (name "unconnected-(DS500-N.C.-Pad39)") (class "Default")
      (node (ref "DS500") (pin "39") (pinfunction "N.C._39") (pintype "passive"))
    )
    (net (code "78") (name "unconnected-(IC500-PadEP)") (class "Default")
      (node (ref "IC500") (pin "EP") (pinfunction "EP_EP") (pintype "passive"))
    )
    (net (code "79") (name "unconnected-(IC501-COM1-Pad7)") (class "Default")
      (node (ref "IC501") (pin "7") (pinfunction "COM1_7") (pintype "passive"))
    )
    (net (code "80") (name "unconnected-(IC501-COM2-Pad8)") (class "Default")
      (node (ref "IC501") (pin "8") (pinfunction "COM2_8") (pintype "passive"))
    )
    (net (code "81") (name "unconnected-(IC501-COM3-Pad9)") (class "Default")
      (node (ref "IC501") (pin "9") (pinfunction "COM3_9") (pintype "passive"))
    )
    (net (code "82") (name "unconnected-(IC501-SEG32-Pad2)") (class "Default")
      (node (ref "IC501") (pin "2") (pinfunction "SEG32_2") (pintype "passive"))
    )
    (net (code "83") (name "unconnected-(IC501-SEG33-Pad3)") (class "Default")
      (node (ref "IC501") (pin "3") (pinfunction "SEG33_3") (pintype "passive"))
    )
    (net (code "84") (name "unconnected-(IC501-SEG34-Pad4)") (class "Default")
      (node (ref "IC501") (pin "4") (pinfunction "SEG34_4") (pintype "passive"))
    )
    (net (code "85") (name "unconnected-(IC501-SEG35-Pad5)") (class "Default")
      (node (ref "IC501") (pin "5") (pinfunction "SEG35_5") (pintype "passive"))
    )
    (net (code "86") (name "unconnected-(IC502-PadEP)") (class "Default")
      (node (ref "IC502") (pin "EP") (pinfunction "EP_EP") (pintype "passive"))
    )
    (net (code "87") (name "unconnected-(IC503-NC-Pad3)") (class "Default")
      (node (ref "IC503") (pin "3") (pinfunction "NC_3") (pintype "passive+no_connect"))
    )
    (net (code "88") (name "unconnected-(IC503-NC-Pad7)") (class "Default")
      (node (ref "IC503") (pin "7") (pinfunction "NC_7") (pintype "passive+no_connect"))
    )
    (net (code "89") (name "unconnected-(IC504-NC-Pad3)") (class "Default")
      (node (ref "IC504") (pin "3") (pinfunction "NC_3") (pintype "passive+no_connect"))
    )
    (net (code "90") (name "unconnected-(IC504-NC-Pad7)") (class "Default")
      (node (ref "IC504") (pin "7") (pinfunction "NC_7") (pintype "passive+no_connect"))
    )
    (net (code "91") (name "unconnected-(IC505-NC-Pad3)") (class "Default")
      (node (ref "IC505") (pin "3") (pinfunction "NC_3") (pintype "passive+no_connect"))
    )
    (net (code "92") (name "unconnected-(IC505-NC-Pad7)") (class "Default")
      (node (ref "IC505") (pin "7") (pinfunction "NC_7") (pintype "passive+no_connect"))
    )
    (net (code "93") (name "unconnected-(SW500-Pad2)") (class "Default")
      (node (ref "SW500") (pin "2") (pinfunction "2_2") (pintype "passive"))
    )
    (net (code "94") (name "unconnected-(SW500-Pad3)") (class "Default")
      (node (ref "SW500") (pin "3") (pinfunction "3_3") (pintype "passive"))
    )
    (net (code "95") (name "unconnected-(SW501-Pad2)") (class "Default")
      (node (ref "SW501") (pin "2") (pinfunction "2_2") (pintype "passive"))
    )
    (net (code "96") (name "unconnected-(SW501-Pad3)") (class "Default")
      (node (ref "SW501") (pin "3") (pinfunction "3_3") (pintype "passive"))
    )
    (net (code "97") (name "unconnected-(SW502-Pad2)") (class "Default")
      (node (ref "SW502") (pin "2") (pinfunction "2_2") (pintype "passive"))
    )
    (net (code "98") (name "unconnected-(SW502-Pad3)") (class "Default")
      (node (ref "SW502") (pin "3") (pinfunction "3_3") (pintype "passive"))
    )
    (net (code "99") (name "unconnected-(SW503-Pad2)") (class "Default")
      (node (ref "SW503") (pin "2") (pinfunction "2_2") (pintype "passive"))
    )
    (net (code "100") (name "unconnected-(SW503-Pad3)") (class "Default")
      (node (ref "SW503") (pin "3") (pinfunction "3_3") (pintype "passive"))
    )
    (net (code "101") (name "unconnected-(SW504-Pad2)") (class "Default")
      (node (ref "SW504") (pin "2") (pinfunction "2_2") (pintype "passive"))
    )
    (net (code "102") (name "unconnected-(SW504-Pad3)") (class "Default")
      (node (ref "SW504") (pin "3") (pinfunction "3_3") (pintype "passive"))
    )
  )
)
